# B2B_connectors.net
KiCad netlist of a schematic drawn in Altium Designer
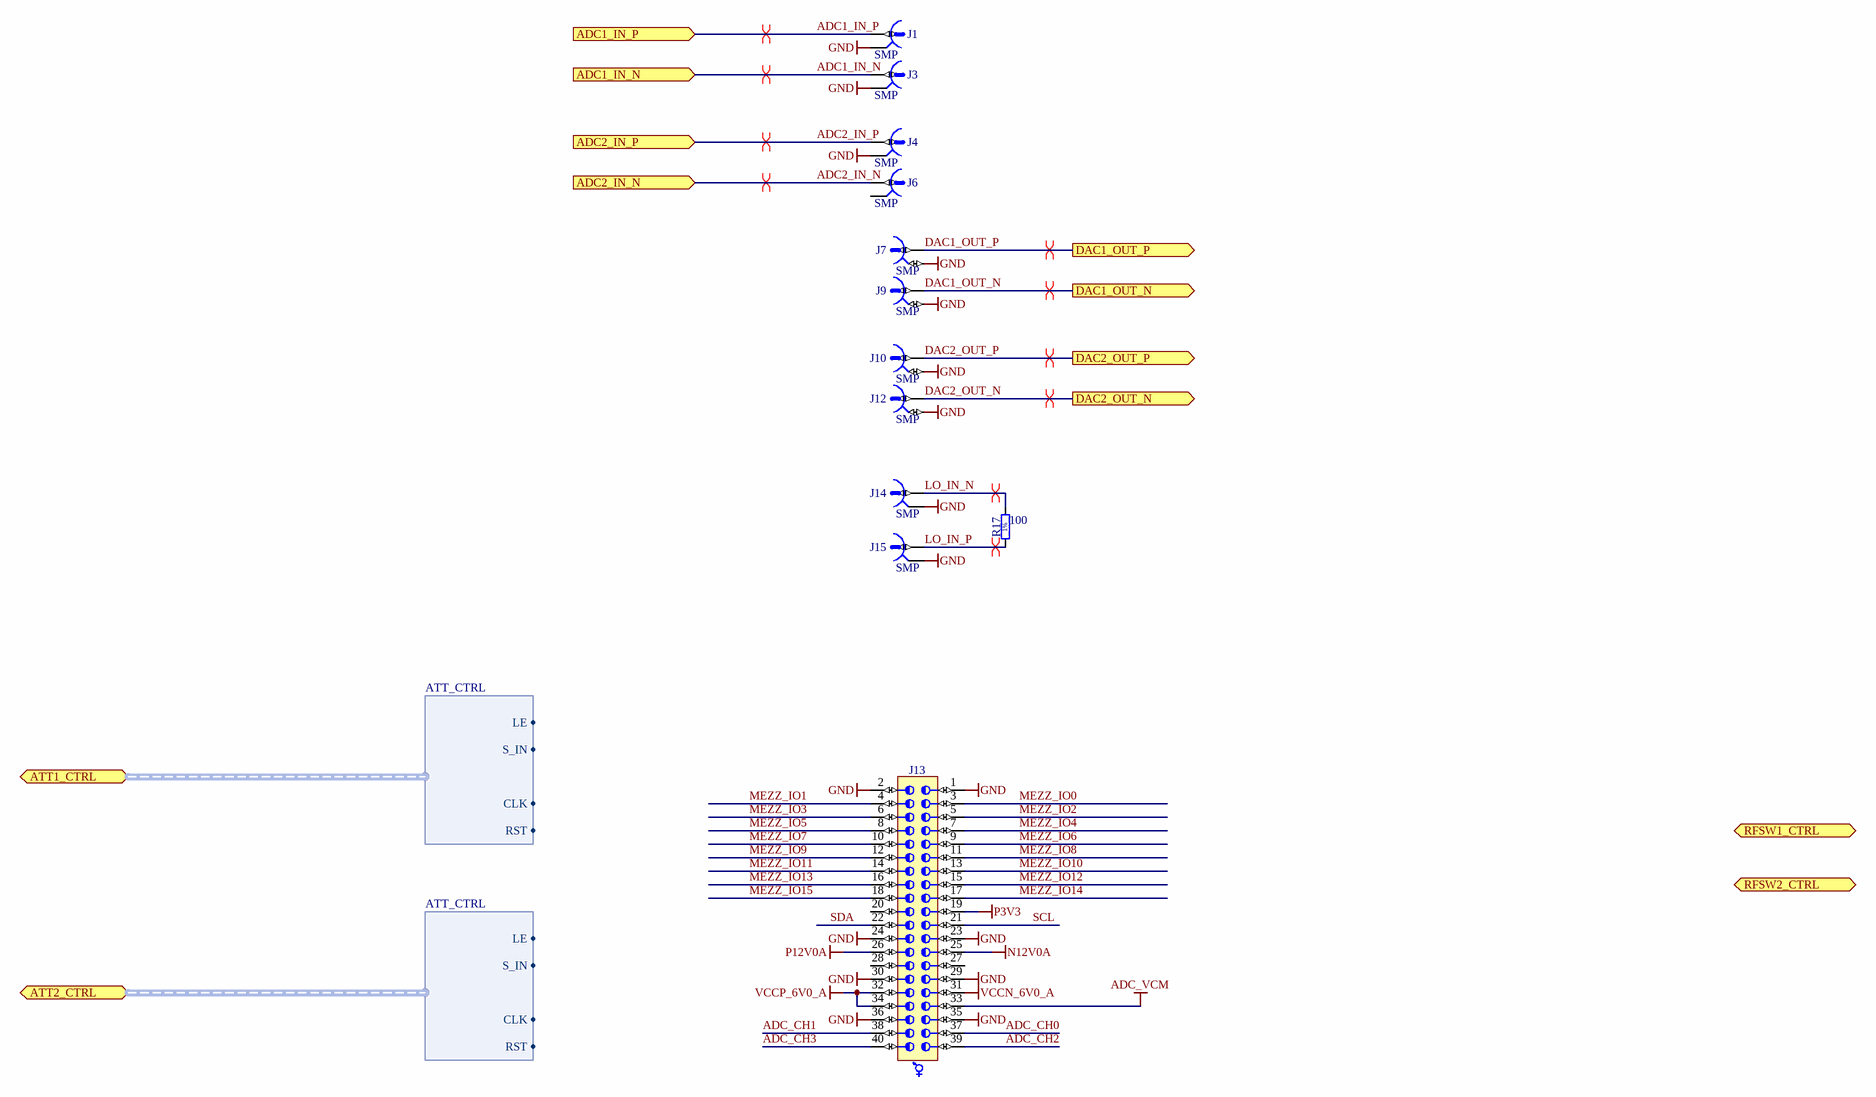
[diagram p0: B2B_connectors .SchDoc]

(export (version "E")
  (design (tool "Eeschema 10.0.6"))
  (components
    (comp (ref "J1")
      (value "SMP")
      (footprint "AMPHENOL_SMP-MSLD-PCT-10")
      (description "50 Ohms, SMP Surface/THT Mount Plug, Limited Detent")
      (fields
        (field (name "PART NUMBER") "AMPHENOL_SMP-MSLD-PCT-10")
        (field (name "MANUFACTURER") "AMPHENOL")
        (field (name "AUTHOR") "GK")
      )
      (libsource (lib "") (part "CON_SMP-MSLD-PCT-10_1"))
    )
    (comp (ref "J3")
      (value "SMP")
      (footprint "AMPHENOL_SMP-MSLD-PCT-10")
      (description "50 Ohms, SMP Surface/THT Mount Plug, Limited Detent")
      (fields
        (field (name "PART NUMBER") "AMPHENOL_SMP-MSLD-PCT-10")
        (field (name "MANUFACTURER") "AMPHENOL")
        (field (name "AUTHOR") "GK")
      )
      (libsource (lib "") (part "CON_SMP-MSLD-PCT-10_1"))
    )
    (comp (ref "J4")
      (value "SMP")
      (footprint "AMPHENOL_SMP-MSLD-PCT-10")
      (description "50 Ohms, SMP Surface/THT Mount Plug, Limited Detent")
      (fields
        (field (name "PART NUMBER") "AMPHENOL_SMP-MSLD-PCT-10")
        (field (name "MANUFACTURER") "AMPHENOL")
        (field (name "AUTHOR") "GK")
      )
      (libsource (lib "") (part "CON_SMP-MSLD-PCT-10_1"))
    )
    (comp (ref "J6")
      (value "SMP")
      (footprint "AMPHENOL_SMP-MSLD-PCT-10")
      (description "50 Ohms, SMP Surface/THT Mount Plug, Limited Detent")
      (fields
        (field (name "PART NUMBER") "AMPHENOL_SMP-MSLD-PCT-10")
        (field (name "MANUFACTURER") "AMPHENOL")
        (field (name "AUTHOR") "GK")
      )
      (libsource (lib "") (part "CON_SMP-MSLD-PCT-10_1"))
    )
    (comp (ref "J7")
      (value "SMP")
      (footprint "MOLEX_85305-0232")
      (fields
        (field (name "PART NUMBER") "MOLEX_85305-0232")
        (field (name "MANUFACTURER") "MOLEX")
        (field (name "MANUFACTURER PART NUMBER") "85305-0232")
        (field (name "AUTHOR") "CERN DEM JMW")
      )
      (libsource (lib "Connectors") (part "Coax_1Male_1Shield"))
    )
    (comp (ref "J9")
      (value "SMP")
      (footprint "MOLEX_85305-0232")
      (fields
        (field (name "PART NUMBER") "MOLEX_85305-0232")
        (field (name "MANUFACTURER") "MOLEX")
        (field (name "MANUFACTURER PART NUMBER") "85305-0232")
        (field (name "AUTHOR") "CERN DEM JMW")
      )
      (libsource (lib "Connectors") (part "Coax_1Male_1Shield"))
    )
    (comp (ref "J10")
      (value "SMP")
      (footprint "MOLEX_85305-0232")
      (fields
        (field (name "PART NUMBER") "MOLEX_85305-0232")
        (field (name "MANUFACTURER") "MOLEX")
        (field (name "MANUFACTURER PART NUMBER") "85305-0232")
        (field (name "AUTHOR") "CERN DEM JMW")
      )
      (libsource (lib "Connectors") (part "Coax_1Male_1Shield"))
    )
    (comp (ref "J12")
      (value "SMP")
      (footprint "MOLEX_85305-0232")
      (fields
        (field (name "PART NUMBER") "MOLEX_85305-0232")
        (field (name "MANUFACTURER") "MOLEX")
        (field (name "MANUFACTURER PART NUMBER") "85305-0232")
        (field (name "AUTHOR") "CERN DEM JMW")
      )
      (libsource (lib "Connectors") (part "Coax_1Male_1Shield"))
    )
    (comp (ref "J13")
      (value "~")
      (footprint "SAMTEC_LSS-120-03-L-DV-A")
      (description "Connector 40 Hermaphroditic")
      (fields
        (field (name "PART NUMBER") "SAMTEC_LSS-120-03-L-DV-A")
        (field (name "MANUFACTURER") "SAMTEC")
        (field (name "AUTHOR") "CERN DEM JMW")
      )
      (libsource (lib "Connectors") (part "Connector 40 Hermaphroditic"))
    )
    (comp (ref "J14")
      (value "SMP")
      (footprint "AMPHENOL_SMP-MSLD-PCT-10")
      (description "50 Ohms, SMP Surface/THT Mount Plug, Limited Detent")
      (fields
        (field (name "PART NUMBER") "AMPHENOL_SMP-MSLD-PCT-10")
        (field (name "MANUFACTURER") "AMPHENOL")
        (field (name "AUTHOR") "GK")
      )
      (libsource (lib "LIBRARY_SCH") (part "CON_SMP-MSLD-PCT-10"))
    )
    (comp (ref "J15")
      (value "SMP")
      (footprint "AMPHENOL_SMP-MSLD-PCT-10")
      (description "50 Ohms, SMP Surface/THT Mount Plug, Limited Detent")
      (fields
        (field (name "PART NUMBER") "AMPHENOL_SMP-MSLD-PCT-10")
        (field (name "MANUFACTURER") "AMPHENOL")
        (field (name "AUTHOR") "GK")
      )
      (libsource (lib "LIBRARY_SCH") (part "CON_SMP-MSLD-PCT-10"))
    )
    (comp (ref "R17")
      (value "100")
      (footprint "RESC1005X40N")
      (description "Resistor - 1%")
      (fields
        (field (name "PART NUMBER") "R0402_100R_1%_0.0625W_100PPM")
        (field (name "POWER") "0.0625W")
        (field (name "AUTHOR") "CERN DEM JLC")
      )
      (libsource (lib "Resistors") (part "Resistor - 1%"))
    )
  )
  (nets
    (net (code "2") (name "/ADC1_IN_N") (class "Default")
      (node (ref "J3") (pin "1") (pinfunction "1_1") (pintype "bidirectional"))
    )
    (net (code "3") (name "/ADC1_IN_P") (class "Default")
      (node (ref "J1") (pin "1") (pinfunction "1_1") (pintype "bidirectional"))
    )
    (net (code "4") (name "/ADC2_IN_N") (class "Default")
      (node (ref "J6") (pin "1") (pinfunction "1_1") (pintype "bidirectional"))
    )
    (net (code "5") (name "/ADC2_IN_P") (class "Default")
      (node (ref "J4") (pin "1") (pinfunction "1_1") (pintype "bidirectional"))
    )
    (net (code "6") (name "/ADC_CH0") (class "Default")
      (node (ref "J13") (pin "37") (pinfunction "37_37") (pintype "bidirectional"))
    )
    (net (code "7") (name "/ADC_CH1") (class "Default")
      (node (ref "J13") (pin "38") (pinfunction "38_38") (pintype "bidirectional"))
    )
    (net (code "8") (name "/ADC_CH2") (class "Default")
      (node (ref "J13") (pin "39") (pinfunction "39_39") (pintype "bidirectional"))
    )
    (net (code "9") (name "/ADC_CH3") (class "Default")
      (node (ref "J13") (pin "40") (pinfunction "40_40") (pintype "bidirectional"))
    )
    (net (code "10") (name "/DAC1_OUT_N") (class "Default")
      (node (ref "J9") (pin "1") (pinfunction "1_1") (pintype "bidirectional"))
    )
    (net (code "11") (name "/DAC1_OUT_P") (class "Default")
      (node (ref "J7") (pin "1") (pinfunction "1_1") (pintype "bidirectional"))
    )
    (net (code "12") (name "/DAC2_OUT_N") (class "Default")
      (node (ref "J12") (pin "1") (pinfunction "1_1") (pintype "bidirectional"))
    )
    (net (code "13") (name "/DAC2_OUT_P") (class "Default")
      (node (ref "J10") (pin "1") (pinfunction "1_1") (pintype "bidirectional"))
    )
    (net (code "14") (name "/LO_IN_N") (class "Default")
      (node (ref "J14") (pin "1") (pinfunction "1_1") (pintype "bidirectional"))
      (node (ref "R17") (pin "2") (pinfunction "2_2") (pintype "passive"))
    )
    (net (code "15") (name "/LO_IN_P") (class "Default")
      (node (ref "J15") (pin "1") (pinfunction "1_1") (pintype "bidirectional"))
      (node (ref "R17") (pin "1") (pinfunction "1_1") (pintype "passive"))
    )
    (net (code "16") (name "/MEZZ_IO0") (class "Default")
      (node (ref "J13") (pin "3") (pinfunction "3_3") (pintype "bidirectional"))
    )
    (net (code "17") (name "/MEZZ_IO1") (class "Default")
      (node (ref "J13") (pin "4") (pinfunction "4_4") (pintype "bidirectional"))
    )
    (net (code "18") (name "/MEZZ_IO2") (class "Default")
      (node (ref "J13") (pin "5") (pinfunction "5_5") (pintype "bidirectional"))
    )
    (net (code "19") (name "/MEZZ_IO3") (class "Default")
      (node (ref "J13") (pin "6") (pinfunction "6_6") (pintype "bidirectional"))
    )
    (net (code "20") (name "/MEZZ_IO4") (class "Default")
      (node (ref "J13") (pin "7") (pinfunction "7_7") (pintype "bidirectional"))
    )
    (net (code "21") (name "/MEZZ_IO5") (class "Default")
      (node (ref "J13") (pin "8") (pinfunction "8_8") (pintype "bidirectional"))
    )
    (net (code "22") (name "/MEZZ_IO6") (class "Default")
      (node (ref "J13") (pin "9") (pinfunction "9_9") (pintype "bidirectional"))
    )
    (net (code "23") (name "/MEZZ_IO7") (class "Default")
      (node (ref "J13") (pin "10") (pinfunction "10_10") (pintype "bidirectional"))
    )
    (net (code "24") (name "/MEZZ_IO8") (class "Default")
      (node (ref "J13") (pin "11") (pinfunction "11_11") (pintype "bidirectional"))
    )
    (net (code "25") (name "/MEZZ_IO9") (class "Default")
      (node (ref "J13") (pin "12") (pinfunction "12_12") (pintype "bidirectional"))
    )
    (net (code "26") (name "/MEZZ_IO10") (class "Default")
      (node (ref "J13") (pin "13") (pinfunction "13_13") (pintype "bidirectional"))
    )
    (net (code "27") (name "/MEZZ_IO11") (class "Default")
      (node (ref "J13") (pin "14") (pinfunction "14_14") (pintype "bidirectional"))
    )
    (net (code "28") (name "/MEZZ_IO12") (class "Default")
      (node (ref "J13") (pin "15") (pinfunction "15_15") (pintype "bidirectional"))
    )
    (net (code "29") (name "/MEZZ_IO13") (class "Default")
      (node (ref "J13") (pin "16") (pinfunction "16_16") (pintype "bidirectional"))
    )
    (net (code "30") (name "/MEZZ_IO14") (class "Default")
      (node (ref "J13") (pin "17") (pinfunction "17_17") (pintype "bidirectional"))
    )
    (net (code "31") (name "/MEZZ_IO15") (class "Default")
      (node (ref "J13") (pin "18") (pinfunction "18_18") (pintype "bidirectional"))
    )
    (net (code "34") (name "/SCL") (class "Default")
      (node (ref "J13") (pin "21") (pinfunction "21_21") (pintype "bidirectional"))
    )
    (net (code "35") (name "/SDA") (class "Default")
      (node (ref "J13") (pin "22") (pinfunction "22_22") (pintype "bidirectional"))
    )
    (net (code "37") (name "ADC_VCM") (class "Default")
      (node (ref "J13") (pin "33") (pinfunction "33_33") (pintype "bidirectional"))
    )
    (net (code "38") (name "GND") (class "Default")
      (node (ref "J1") (pin "2") (pinfunction "2_2") (pintype "passive"))
      (node (ref "J10") (pin "2") (pinfunction "2_2") (pintype "bidirectional"))
      (node (ref "J12") (pin "2") (pinfunction "2_2") (pintype "bidirectional"))
      (node (ref "J13") (pin "1") (pinfunction "1_1") (pintype "bidirectional"))
      (node (ref "J13") (pin "2") (pinfunction "2_2") (pintype "bidirectional"))
      (node (ref "J13") (pin "23") (pinfunction "23_23") (pintype "bidirectional"))
      (node (ref "J13") (pin "24") (pinfunction "24_24") (pintype "bidirectional"))
      (node (ref "J13") (pin "29") (pinfunction "29_29") (pintype "bidirectional"))
      (node (ref "J13") (pin "30") (pinfunction "30_30") (pintype "bidirectional"))
      (node (ref "J13") (pin "35") (pinfunction "35_35") (pintype "bidirectional"))
      (node (ref "J13") (pin "36") (pinfunction "36_36") (pintype "bidirectional"))
      (node (ref "J14") (pin "2") (pinfunction "2_2") (pintype "passive"))
      (node (ref "J15") (pin "2") (pinfunction "2_2") (pintype "passive"))
      (node (ref "J3") (pin "2") (pinfunction "2_2") (pintype "passive"))
      (node (ref "J4") (pin "2") (pinfunction "2_2") (pintype "passive"))
      (node (ref "J7") (pin "2") (pinfunction "2_2") (pintype "bidirectional"))
      (node (ref "J9") (pin "2") (pinfunction "2_2") (pintype "bidirectional"))
    )
    (net (code "39") (name "N12V0A") (class "Default")
      (node (ref "J13") (pin "25") (pinfunction "25_25") (pintype "bidirectional"))
    )
    (net (code "40") (name "P3V3") (class "Default")
      (node (ref "J13") (pin "19") (pinfunction "19_19") (pintype "bidirectional"))
    )
    (net (code "41") (name "P12V0A") (class "Default")
      (node (ref "J13") (pin "26") (pinfunction "26_26") (pintype "bidirectional"))
    )
    (net (code "42") (name "VCCN_6V0_A") (class "Default")
      (node (ref "J13") (pin "31") (pinfunction "31_31") (pintype "bidirectional"))
    )
    (net (code "43") (name "VCCP_6V0_A") (class "Default")
      (node (ref "J13") (pin "32") (pinfunction "32_32") (pintype "bidirectional"))
      (node (ref "J13") (pin "34") (pinfunction "34_34") (pintype "bidirectional"))
    )
    (net (code "44") (name "unconnected-(J6-Pad2)") (class "Default")
      (node (ref "J6") (pin "2") (pinfunction "2_2") (pintype "passive"))
    )
    (net (code "45") (name "unconnected-(J13-Pad20)") (class "Default")
      (node (ref "J13") (pin "20") (pinfunction "20_20") (pintype "bidirectional"))
    )
    (net (code "46") (name "unconnected-(J13-Pad27)") (class "Default")
      (node (ref "J13") (pin "27") (pinfunction "27_27") (pintype "bidirectional"))
    )
    (net (code "47") (name "unconnected-(J13-Pad28)") (class "Default")
      (node (ref "J13") (pin "28") (pinfunction "28_28") (pintype "bidirectional"))
    )
  )
)
